# em_probe.net
KiCad netlist of a schematic drawn in EAGLE
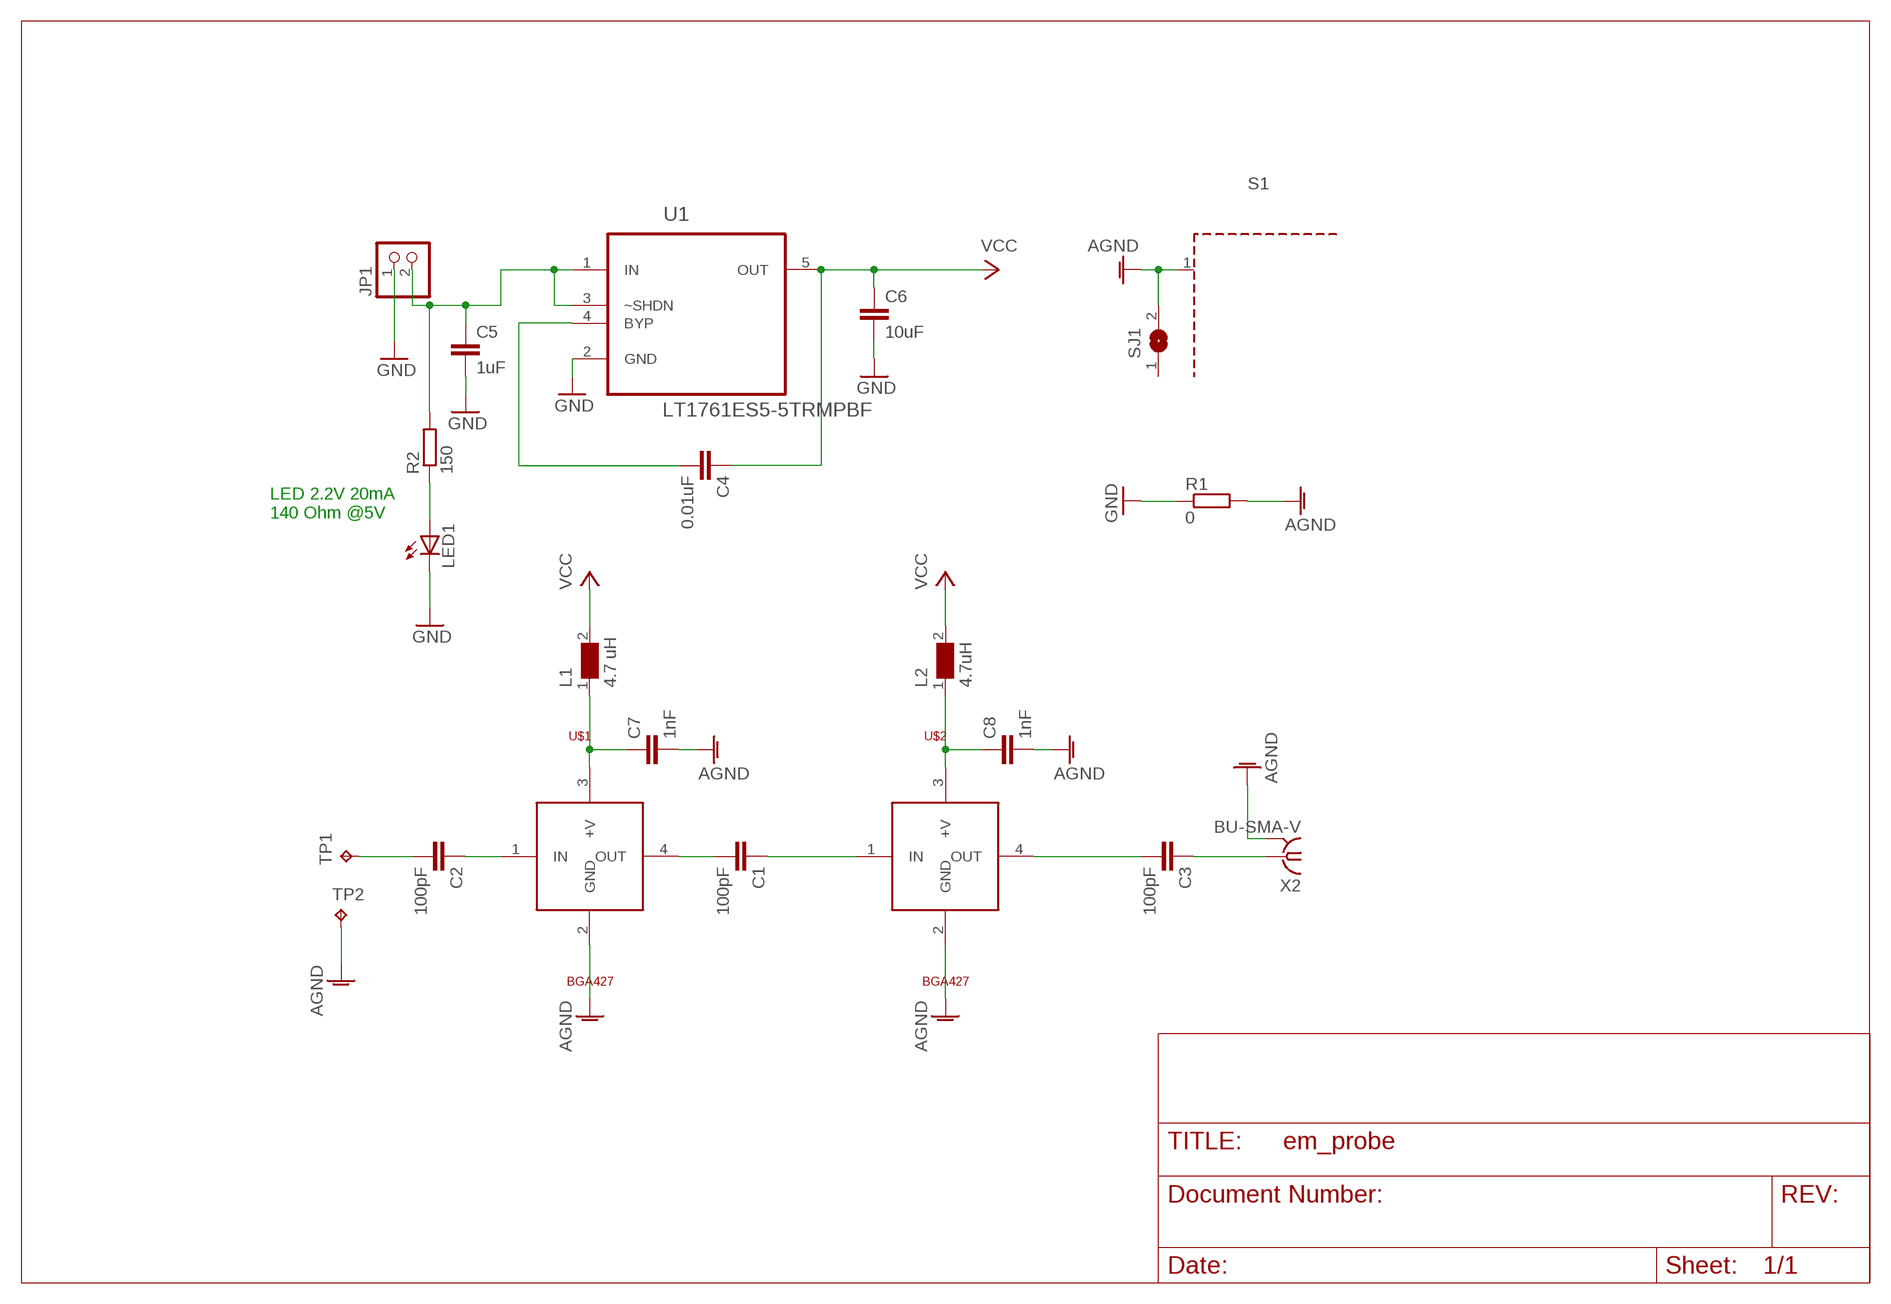
[diagram p0: schematic, sheet 1]

(export (version "E")
  (design (tool "Eeschema 10.0.6"))
  (components
    (comp (ref "C1")
      (value "100pF")
      (footprint "eagle-import:C0805")
      (libsource (lib "eagle-import") (part "C-EUC0805"))
    )
    (comp (ref "C2")
      (value "100pF")
      (footprint "eagle-import:C0805")
      (libsource (lib "eagle-import") (part "C-EUC0805"))
    )
    (comp (ref "C3")
      (value "100pF")
      (footprint "eagle-import:C0805")
      (libsource (lib "eagle-import") (part "C-EUC0805"))
    )
    (comp (ref "C4")
      (value "0.01uF")
      (footprint "eagle-import:C0805")
      (libsource (lib "eagle-import") (part "C-EUC0805"))
    )
    (comp (ref "C5")
      (value "1uF")
      (footprint "eagle-import:C0805")
      (libsource (lib "eagle-import") (part "C-EUC0805"))
    )
    (comp (ref "C6")
      (value "10uF")
      (footprint "eagle-import:C0805")
      (libsource (lib "eagle-import") (part "C-EUC0805"))
    )
    (comp (ref "C7")
      (value "1nF")
      (footprint "eagle-import:C0805")
      (libsource (lib "eagle-import") (part "C-EUC0805"))
    )
    (comp (ref "C8")
      (value "1nF")
      (footprint "eagle-import:C0805")
      (libsource (lib "eagle-import") (part "C-EUC0805"))
    )
    (comp (ref "JP1")
      (value "PINHD-1X2/90")
      (footprint "eagle-import:1X02_90")
      (libsource (lib "eagle-import") (part "PINHD-1X2/90"))
    )
    (comp (ref "L1")
      (value "4.7 uH")
      (footprint "eagle-import:WE-RFH")
      (fields (field (name "MPN") "744758347A"))
      (libsource (lib "eagle-import") (part "WE-RFH-744758347A"))
    )
    (comp (ref "L2")
      (value "4.7uH")
      (footprint "eagle-import:WE-RFH")
      (fields (field (name "MPN") "744758347A"))
      (libsource (lib "eagle-import") (part "WE-RFH-744758347A"))
    )
    (comp (ref "LED1")
      (value "LEDCHIPLED_0805")
      (footprint "eagle-import:CHIPLED_0805")
      (libsource (lib "eagle-import") (part "LEDCHIPLED_0805"))
    )
    (comp (ref "R1")
      (value "0")
      (footprint "eagle-import:R0805")
      (libsource (lib "eagle-import") (part "R-EU_R0805"))
    )
    (comp (ref "R2")
      (value "150")
      (footprint "eagle-import:R0805")
      (libsource (lib "eagle-import") (part "R-EU_R0805"))
    )
    (comp (ref "S1")
      (value "WE-SHC_36103305")
      (footprint "eagle-import:WE-SHC_36103305")
      (fields (field (name "MPN") "36103305"))
      (libsource (lib "eagle-import") (part "WE-SHC_36103305"))
    )
    (comp (ref "SJ1") (value "SJ") (footprint "eagle-import:SJ") (libsource (lib "eagle-import") (part "SJ")))
    (comp (ref "TP1")
      (value "TPTP15R")
      (footprint "eagle-import:TP15R")
      (libsource (lib "eagle-import") (part "TPTP15R"))
    )
    (comp (ref "TP2")
      (value "TPTP15R")
      (footprint "eagle-import:TP15R")
      (libsource (lib "eagle-import") (part "TPTP15R"))
    )
    (comp (ref "U$1")
      (value "BGA427")
      (footprint "eagle-import:SOT343")
      (libsource (lib "eagle-import") (part "BGA427"))
    )
    (comp (ref "U$2")
      (value "BGA427")
      (footprint "eagle-import:SOT343")
      (libsource (lib "eagle-import") (part "BGA427"))
    )
    (comp (ref "U1")
      (value "LT1761ES5-5TRMPBF")
      (footprint "eagle-import:SOT95P280X100-5N")
      (fields (field (name "MPN") "LT1761ES5-5#TRMPBF"))
      (libsource (lib "eagle-import") (part "LT1761ES5-5TRMPBF"))
    )
    (comp (ref "X2")
      (value "BU-SMA-V")
      (footprint "eagle-import:BU-SMA-V")
      (libsource (lib "eagle-import") (part "BU-SMA-V"))
    )
  )
  (nets
    (net (code "1") (name "AGND") (class "Default")
      (node (ref "C7") (pin "2") (pinfunction "2_2") (pintype "passive"))
      (node (ref "C8") (pin "2") (pinfunction "2_2") (pintype "passive"))
      (node (ref "R1") (pin "2") (pinfunction "2_2") (pintype "passive"))
      (node (ref "S1") (pin "1") (pinfunction "GND_1") (pintype "power_in"))
      (node (ref "SJ1") (pin "2") (pinfunction "2_2") (pintype "passive"))
      (node (ref "TP2") (pin "TP") (pinfunction "TP_TP") (pintype "input"))
      (node (ref "U$1") (pin "2") (pinfunction "GND_2") (pintype "bidirectional"))
      (node (ref "U$2") (pin "2") (pinfunction "GND_2") (pintype "bidirectional"))
      (node (ref "X2") (pin "2") (pinfunction "2_2") (pintype "passive"))
      (node (ref "X2") (pin "3") (pinfunction "2_3") (pintype "passive"))
      (node (ref "X2") (pin "4") (pinfunction "2_4") (pintype "passive"))
      (node (ref "X2") (pin "5") (pinfunction "2_5") (pintype "passive"))
    )
    (net (code "2") (name "GND") (class "Default")
      (node (ref "C5") (pin "2") (pinfunction "2_2") (pintype "passive"))
      (node (ref "C6") (pin "2") (pinfunction "2_2") (pintype "passive"))
      (node (ref "JP1") (pin "1") (pinfunction "1_1") (pintype "passive"))
      (node (ref "LED1") (pin "C") (pinfunction "C_C") (pintype "passive"))
      (node (ref "R1") (pin "1") (pinfunction "1_1") (pintype "passive"))
      (node (ref "U1") (pin "2") (pinfunction "GND_2") (pintype "passive"))
    )
    (net (code "3") (name "Net-(C2-Pad2)") (class "Default")
      (node (ref "C2") (pin "2") (pinfunction "2_2") (pintype "passive"))
      (node (ref "TP1") (pin "TP") (pinfunction "TP_TP") (pintype "input"))
    )
    (net (code "4") (name "Net-(C3-Pad1)") (class "Default")
      (node (ref "C3") (pin "1") (pinfunction "1_1") (pintype "passive"))
      (node (ref "X2") (pin "1") (pinfunction "1_1") (pintype "passive"))
    )
    (net (code "5") (name "Net-(LED1-PadA)") (class "Default")
      (node (ref "LED1") (pin "A") (pinfunction "A_A") (pintype "passive"))
      (node (ref "R2") (pin "1") (pinfunction "1_1") (pintype "passive"))
    )
    (net (code "6") (name "Net-(U$1-+V)") (class "Default")
      (node (ref "C7") (pin "1") (pinfunction "1_1") (pintype "passive"))
      (node (ref "L1") (pin "1") (pinfunction "1_1") (pintype "passive"))
      (node (ref "U$1") (pin "3") (pinfunction "+V_3") (pintype "bidirectional"))
    )
    (net (code "7") (name "Net-(U$1-IN)") (class "Default")
      (node (ref "C2") (pin "1") (pinfunction "1_1") (pintype "passive"))
      (node (ref "U$1") (pin "1") (pinfunction "IN_1") (pintype "bidirectional"))
    )
    (net (code "8") (name "Net-(U$1-OUT)") (class "Default")
      (node (ref "C1") (pin "2") (pinfunction "2_2") (pintype "passive"))
      (node (ref "U$1") (pin "4") (pinfunction "OUT_4") (pintype "bidirectional"))
    )
    (net (code "9") (name "Net-(U$2-+V)") (class "Default")
      (node (ref "C8") (pin "1") (pinfunction "1_1") (pintype "passive"))
      (node (ref "L2") (pin "1") (pinfunction "1_1") (pintype "passive"))
      (node (ref "U$2") (pin "3") (pinfunction "+V_3") (pintype "bidirectional"))
    )
    (net (code "10") (name "Net-(U$2-IN)") (class "Default")
      (node (ref "C1") (pin "1") (pinfunction "1_1") (pintype "passive"))
      (node (ref "U$2") (pin "1") (pinfunction "IN_1") (pintype "bidirectional"))
    )
    (net (code "11") (name "Net-(U$2-OUT)") (class "Default")
      (node (ref "C3") (pin "2") (pinfunction "2_2") (pintype "passive"))
      (node (ref "U$2") (pin "4") (pinfunction "OUT_4") (pintype "bidirectional"))
    )
    (net (code "12") (name "Net-(U1-BYP)") (class "Default")
      (node (ref "C4") (pin "2") (pinfunction "2_2") (pintype "passive"))
      (node (ref "U1") (pin "4") (pinfunction "BYP_4") (pintype "input"))
    )
    (net (code "13") (name "Net-(U1-IN)") (class "Default")
      (node (ref "C5") (pin "1") (pinfunction "1_1") (pintype "passive"))
      (node (ref "JP1") (pin "2") (pinfunction "2_2") (pintype "passive"))
      (node (ref "R2") (pin "2") (pinfunction "2_2") (pintype "passive"))
      (node (ref "U1") (pin "1") (pinfunction "IN_1") (pintype "input"))
      (node (ref "U1") (pin "3") (pinfunction "~{SHDN}_3") (pintype "input"))
    )
    (net (code "14") (name "VCC") (class "Default")
      (node (ref "C4") (pin "1") (pinfunction "1_1") (pintype "passive"))
      (node (ref "C6") (pin "1") (pinfunction "1_1") (pintype "passive"))
      (node (ref "L1") (pin "2") (pinfunction "2_2") (pintype "passive"))
      (node (ref "L2") (pin "2") (pinfunction "2_2") (pintype "passive"))
      (node (ref "U1") (pin "5") (pinfunction "OUT_5") (pintype "output"))
    )
    (net (code "15") (name "unconnected-(SJ1-Pad1)") (class "Default")
      (node (ref "SJ1") (pin "1") (pinfunction "1_1") (pintype "passive"))
    )
  )
)
